# backplane-rev2.net
KiCad netlist of a schematic drawn in EAGLE
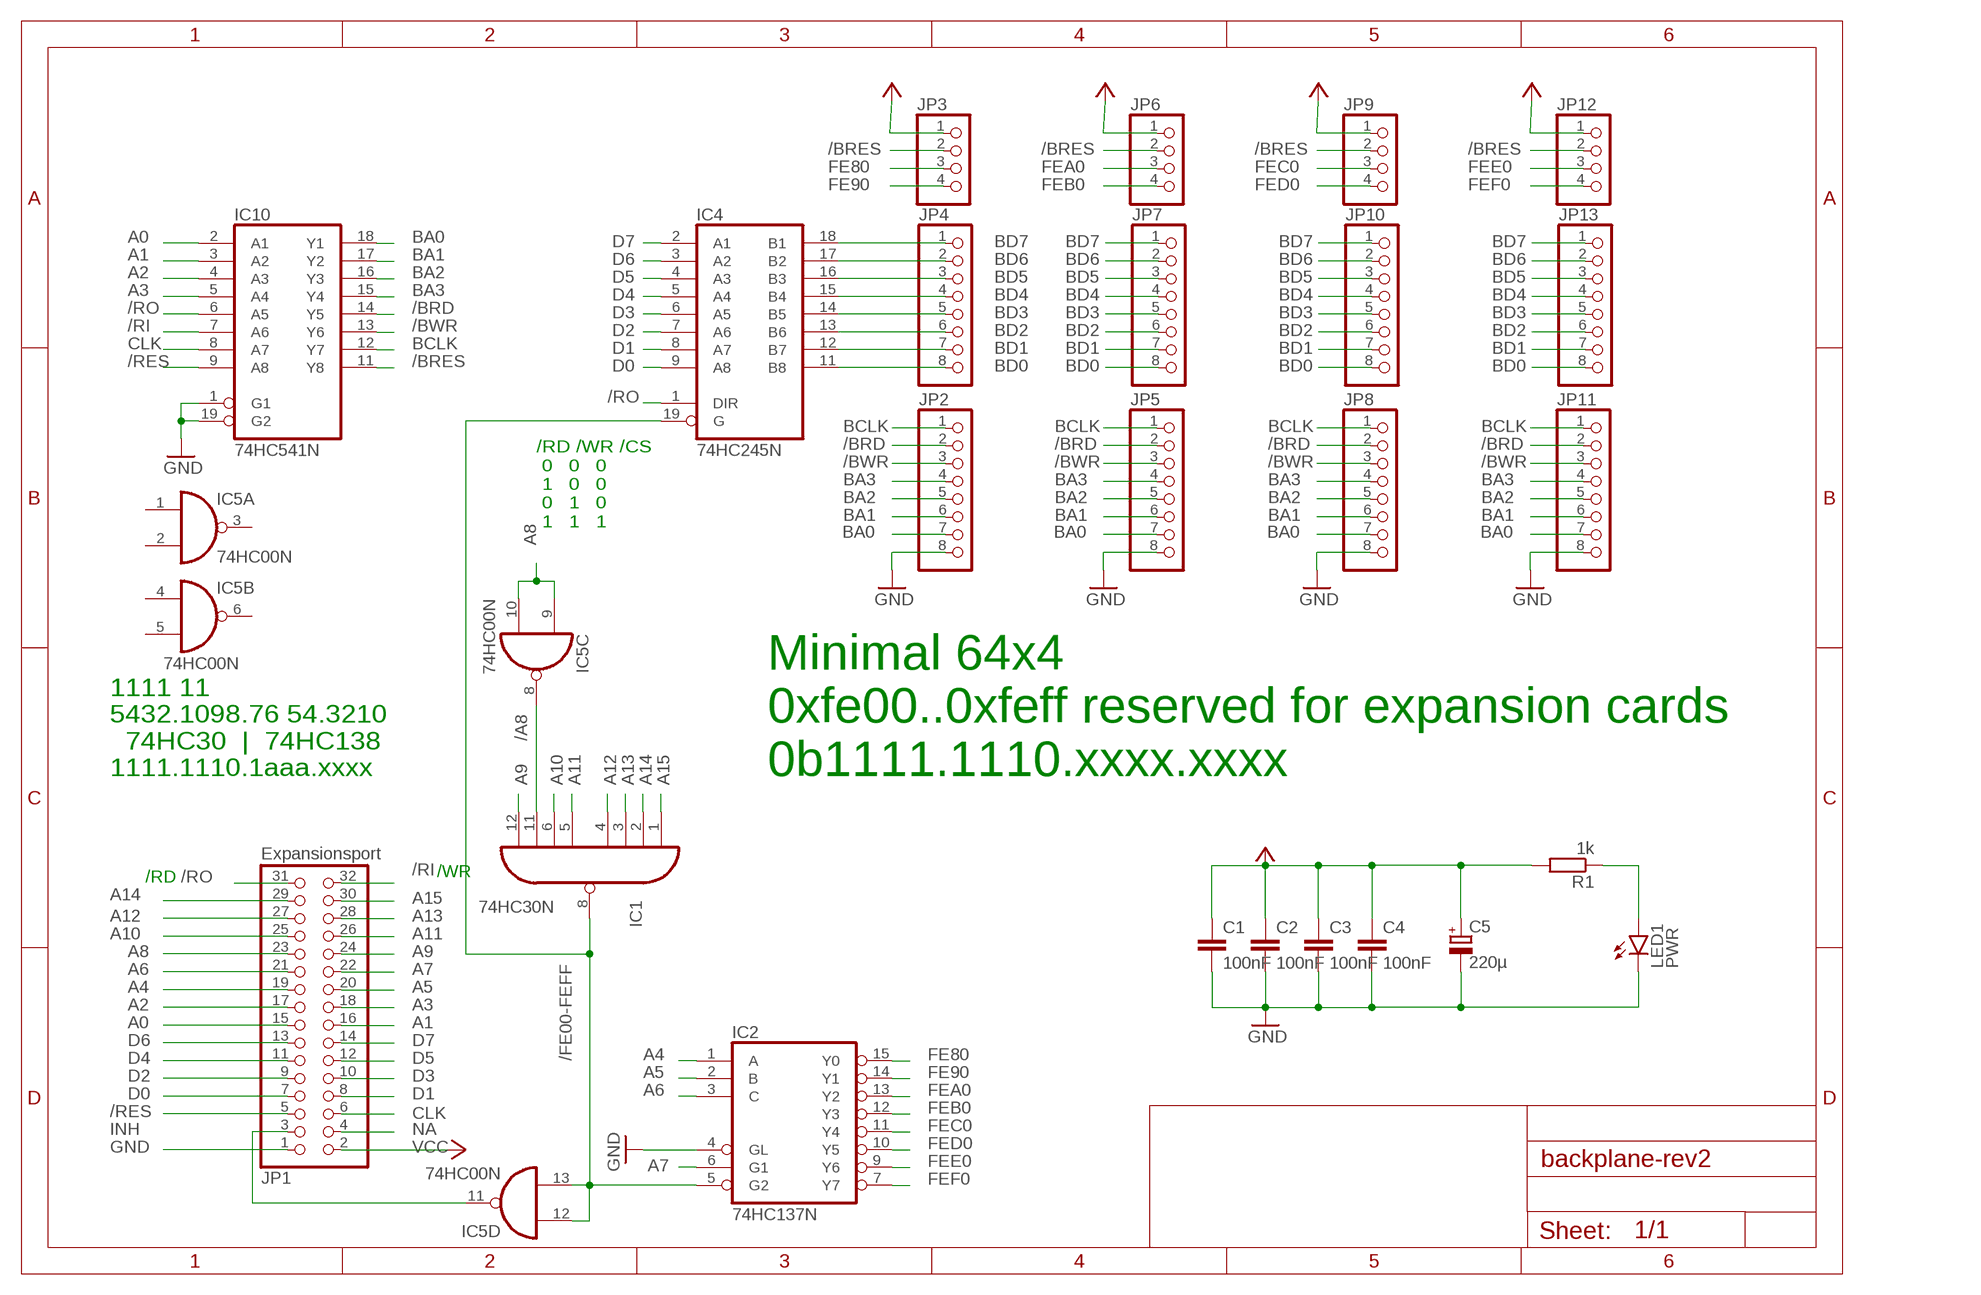
[diagram p0: schematic, sheet 1]

(export (version "E")
  (design (tool "Eeschema 10.0.6"))
  (components
    (comp (ref "C1")
      (value "100nF")
      (footprint "eagle-import:C050-025X075")
      (libsource (lib "eagle-import") (part "C-EU050-025X075"))
    )
    (comp (ref "C2")
      (value "100nF")
      (footprint "eagle-import:C050-025X075")
      (libsource (lib "eagle-import") (part "C-EU050-025X075"))
    )
    (comp (ref "C3")
      (value "100nF")
      (footprint "eagle-import:C050-025X075")
      (libsource (lib "eagle-import") (part "C-EU050-025X075"))
    )
    (comp (ref "C4")
      (value "100nF")
      (footprint "eagle-import:C050-025X075")
      (libsource (lib "eagle-import") (part "C-EU050-025X075"))
    )
    (comp (ref "C5")
      (value "220µ")
      (footprint "eagle-import:E3,5-8")
      (libsource (lib "eagle-import") (part "CPOL-EUE3.5-8"))
    )
    (comp (ref "IC1")
      (value "74HC30N")
      (footprint "eagle-import:DIL14")
      (libsource (lib "eagle-import") (part "7430NHC"))
    )
    (comp (ref "IC2")
      (value "74HC137N")
      (footprint "eagle-import:DIL16")
      (libsource (lib "eagle-import") (part "74137NHC"))
    )
    (comp (ref "IC4")
      (value "74HC245N")
      (footprint "eagle-import:DIL20")
      (libsource (lib "eagle-import") (part "74245NHC"))
    )
    (comp (ref "IC5")
      (value "74HC00N")
      (footprint "eagle-import:DIL14")
      (libsource (lib "eagle-import") (part "7400NHC"))
    )
    (comp (ref "IC10")
      (value "74HC541N")
      (footprint "eagle-import:DIL20")
      (libsource (lib "eagle-import") (part "74541NHC"))
    )
    (comp (ref "JP1")
      (value "Expansionsport")
      (footprint "eagle-import:2X16")
      (libsource (lib "eagle-import") (part "PINHD-2X16"))
    )
    (comp (ref "JP2")
      (value "PINHD-1X8")
      (footprint "eagle-import:1X08")
      (libsource (lib "eagle-import") (part "PINHD-1X8"))
    )
    (comp (ref "JP3")
      (value "PINHD-1X4")
      (footprint "eagle-import:1X04")
      (libsource (lib "eagle-import") (part "PINHD-1X4"))
    )
    (comp (ref "JP4")
      (value "PINHD-1X8")
      (footprint "eagle-import:1X08")
      (libsource (lib "eagle-import") (part "PINHD-1X8"))
    )
    (comp (ref "JP5")
      (value "PINHD-1X8")
      (footprint "eagle-import:1X08")
      (libsource (lib "eagle-import") (part "PINHD-1X8"))
    )
    (comp (ref "JP6")
      (value "PINHD-1X4")
      (footprint "eagle-import:1X04")
      (libsource (lib "eagle-import") (part "PINHD-1X4"))
    )
    (comp (ref "JP7")
      (value "PINHD-1X8")
      (footprint "eagle-import:1X08")
      (libsource (lib "eagle-import") (part "PINHD-1X8"))
    )
    (comp (ref "JP8")
      (value "PINHD-1X8")
      (footprint "eagle-import:1X08")
      (libsource (lib "eagle-import") (part "PINHD-1X8"))
    )
    (comp (ref "JP9")
      (value "PINHD-1X4")
      (footprint "eagle-import:1X04")
      (libsource (lib "eagle-import") (part "PINHD-1X4"))
    )
    (comp (ref "JP10")
      (value "PINHD-1X8")
      (footprint "eagle-import:1X08")
      (libsource (lib "eagle-import") (part "PINHD-1X8"))
    )
    (comp (ref "JP11")
      (value "PINHD-1X8")
      (footprint "eagle-import:1X08")
      (libsource (lib "eagle-import") (part "PINHD-1X8"))
    )
    (comp (ref "JP12")
      (value "PINHD-1X4")
      (footprint "eagle-import:1X04")
      (libsource (lib "eagle-import") (part "PINHD-1X4"))
    )
    (comp (ref "JP13")
      (value "PINHD-1X8")
      (footprint "eagle-import:1X08")
      (libsource (lib "eagle-import") (part "PINHD-1X8"))
    )
    (comp (ref "LED1")
      (value "PWR")
      (footprint "eagle-import:LED3MM")
      (libsource (lib "eagle-import") (part "LED3MM"))
    )
    (comp (ref "R1")
      (value "1k")
      (footprint "eagle-import:0207_10")
      (libsource (lib "eagle-import") (part "R-EU_0207/10"))
    )
  )
  (nets
    (net (code "1") (name "/A0") (class "Default")
      (node (ref "IC10") (pin "2") (pinfunction "A1_2") (pintype "input"))
      (node (ref "JP1") (pin "15") (pinfunction "15_15") (pintype "passive"))
    )
    (net (code "2") (name "/A1") (class "Default")
      (node (ref "IC10") (pin "3") (pinfunction "A2_3") (pintype "input"))
      (node (ref "JP1") (pin "16") (pinfunction "16_16") (pintype "passive"))
    )
    (net (code "3") (name "/A2") (class "Default")
      (node (ref "IC10") (pin "4") (pinfunction "A3_4") (pintype "input"))
      (node (ref "JP1") (pin "17") (pinfunction "17_17") (pintype "passive"))
    )
    (net (code "4") (name "/A3") (class "Default")
      (node (ref "IC10") (pin "5") (pinfunction "A4_5") (pintype "input"))
      (node (ref "JP1") (pin "18") (pinfunction "18_18") (pintype "passive"))
    )
    (net (code "5") (name "/A4") (class "Default")
      (node (ref "IC2") (pin "1") (pinfunction "A_1") (pintype "input"))
      (node (ref "JP1") (pin "19") (pinfunction "19_19") (pintype "passive"))
    )
    (net (code "6") (name "/A5") (class "Default")
      (node (ref "IC2") (pin "2") (pinfunction "B_2") (pintype "input"))
      (node (ref "JP1") (pin "20") (pinfunction "20_20") (pintype "passive"))
    )
    (net (code "7") (name "/A6") (class "Default")
      (node (ref "IC2") (pin "3") (pinfunction "C_3") (pintype "input"))
      (node (ref "JP1") (pin "21") (pinfunction "21_21") (pintype "passive"))
    )
    (net (code "8") (name "/A7") (class "Default")
      (node (ref "IC2") (pin "6") (pinfunction "G1_6") (pintype "input"))
      (node (ref "JP1") (pin "22") (pinfunction "22_22") (pintype "passive"))
    )
    (net (code "9") (name "/A8") (class "Default")
      (node (ref "IC5") (pin "10") (pinfunction "I1_10") (pintype "input"))
      (node (ref "IC5") (pin "9") (pinfunction "I0_9") (pintype "input"))
      (node (ref "JP1") (pin "23") (pinfunction "23_23") (pintype "passive"))
    )
    (net (code "10") (name "/A9") (class "Default")
      (node (ref "IC1") (pin "12") (pinfunction "I7_12") (pintype "input"))
      (node (ref "JP1") (pin "24") (pinfunction "24_24") (pintype "passive"))
    )
    (net (code "11") (name "/A10") (class "Default")
      (node (ref "IC1") (pin "6") (pinfunction "I5_6") (pintype "input"))
      (node (ref "JP1") (pin "25") (pinfunction "25_25") (pintype "passive"))
    )
    (net (code "12") (name "/A11") (class "Default")
      (node (ref "IC1") (pin "5") (pinfunction "I4_5") (pintype "input"))
      (node (ref "JP1") (pin "26") (pinfunction "26_26") (pintype "passive"))
    )
    (net (code "13") (name "/A12") (class "Default")
      (node (ref "IC1") (pin "4") (pinfunction "I3_4") (pintype "input"))
      (node (ref "JP1") (pin "27") (pinfunction "27_27") (pintype "passive"))
    )
    (net (code "14") (name "/A13") (class "Default")
      (node (ref "IC1") (pin "3") (pinfunction "I2_3") (pintype "input"))
      (node (ref "JP1") (pin "28") (pinfunction "28_28") (pintype "passive"))
    )
    (net (code "15") (name "/A14") (class "Default")
      (node (ref "IC1") (pin "2") (pinfunction "I1_2") (pintype "input"))
      (node (ref "JP1") (pin "29") (pinfunction "29_29") (pintype "passive"))
    )
    (net (code "16") (name "/A15") (class "Default")
      (node (ref "IC1") (pin "1") (pinfunction "I0_1") (pintype "input"))
      (node (ref "JP1") (pin "30") (pinfunction "30_30") (pintype "passive"))
    )
    (net (code "17") (name "/BA0") (class "Default")
      (node (ref "IC10") (pin "18") (pinfunction "Y1_18") (pintype "tri_state"))
      (node (ref "JP11") (pin "7") (pinfunction "7_7") (pintype "passive"))
      (node (ref "JP2") (pin "7") (pinfunction "7_7") (pintype "passive"))
      (node (ref "JP5") (pin "7") (pinfunction "7_7") (pintype "passive"))
      (node (ref "JP8") (pin "7") (pinfunction "7_7") (pintype "passive"))
    )
    (net (code "18") (name "/BA1") (class "Default")
      (node (ref "IC10") (pin "17") (pinfunction "Y2_17") (pintype "tri_state"))
      (node (ref "JP11") (pin "6") (pinfunction "6_6") (pintype "passive"))
      (node (ref "JP2") (pin "6") (pinfunction "6_6") (pintype "passive"))
      (node (ref "JP5") (pin "6") (pinfunction "6_6") (pintype "passive"))
      (node (ref "JP8") (pin "6") (pinfunction "6_6") (pintype "passive"))
    )
    (net (code "19") (name "/BA2") (class "Default")
      (node (ref "IC10") (pin "16") (pinfunction "Y3_16") (pintype "tri_state"))
      (node (ref "JP11") (pin "5") (pinfunction "5_5") (pintype "passive"))
      (node (ref "JP2") (pin "5") (pinfunction "5_5") (pintype "passive"))
      (node (ref "JP5") (pin "5") (pinfunction "5_5") (pintype "passive"))
      (node (ref "JP8") (pin "5") (pinfunction "5_5") (pintype "passive"))
    )
    (net (code "20") (name "/BA3") (class "Default")
      (node (ref "IC10") (pin "15") (pinfunction "Y4_15") (pintype "tri_state"))
      (node (ref "JP11") (pin "4") (pinfunction "4_4") (pintype "passive"))
      (node (ref "JP2") (pin "4") (pinfunction "4_4") (pintype "passive"))
      (node (ref "JP5") (pin "4") (pinfunction "4_4") (pintype "passive"))
      (node (ref "JP8") (pin "4") (pinfunction "4_4") (pintype "passive"))
    )
    (net (code "21") (name "/BCLK") (class "Default")
      (node (ref "IC10") (pin "12") (pinfunction "Y7_12") (pintype "tri_state"))
      (node (ref "JP11") (pin "1") (pinfunction "1_1") (pintype "passive"))
      (node (ref "JP2") (pin "1") (pinfunction "1_1") (pintype "passive"))
      (node (ref "JP5") (pin "1") (pinfunction "1_1") (pintype "passive"))
      (node (ref "JP8") (pin "1") (pinfunction "1_1") (pintype "passive"))
    )
    (net (code "22") (name "/BD0") (class "Default")
      (node (ref "IC4") (pin "11") (pinfunction "B8_11") (pintype "bidirectional"))
      (node (ref "JP10") (pin "8") (pinfunction "8_8") (pintype "passive"))
      (node (ref "JP13") (pin "8") (pinfunction "8_8") (pintype "passive"))
      (node (ref "JP4") (pin "8") (pinfunction "8_8") (pintype "passive"))
      (node (ref "JP7") (pin "8") (pinfunction "8_8") (pintype "passive"))
    )
    (net (code "23") (name "/BD1") (class "Default")
      (node (ref "IC4") (pin "12") (pinfunction "B7_12") (pintype "bidirectional"))
      (node (ref "JP10") (pin "7") (pinfunction "7_7") (pintype "passive"))
      (node (ref "JP13") (pin "7") (pinfunction "7_7") (pintype "passive"))
      (node (ref "JP4") (pin "7") (pinfunction "7_7") (pintype "passive"))
      (node (ref "JP7") (pin "7") (pinfunction "7_7") (pintype "passive"))
    )
    (net (code "24") (name "/BD2") (class "Default")
      (node (ref "IC4") (pin "13") (pinfunction "B6_13") (pintype "bidirectional"))
      (node (ref "JP10") (pin "6") (pinfunction "6_6") (pintype "passive"))
      (node (ref "JP13") (pin "6") (pinfunction "6_6") (pintype "passive"))
      (node (ref "JP4") (pin "6") (pinfunction "6_6") (pintype "passive"))
      (node (ref "JP7") (pin "6") (pinfunction "6_6") (pintype "passive"))
    )
    (net (code "25") (name "/BD3") (class "Default")
      (node (ref "IC4") (pin "14") (pinfunction "B5_14") (pintype "bidirectional"))
      (node (ref "JP10") (pin "5") (pinfunction "5_5") (pintype "passive"))
      (node (ref "JP13") (pin "5") (pinfunction "5_5") (pintype "passive"))
      (node (ref "JP4") (pin "5") (pinfunction "5_5") (pintype "passive"))
      (node (ref "JP7") (pin "5") (pinfunction "5_5") (pintype "passive"))
    )
    (net (code "26") (name "/BD4") (class "Default")
      (node (ref "IC4") (pin "15") (pinfunction "B4_15") (pintype "bidirectional"))
      (node (ref "JP10") (pin "4") (pinfunction "4_4") (pintype "passive"))
      (node (ref "JP13") (pin "4") (pinfunction "4_4") (pintype "passive"))
      (node (ref "JP4") (pin "4") (pinfunction "4_4") (pintype "passive"))
      (node (ref "JP7") (pin "4") (pinfunction "4_4") (pintype "passive"))
    )
    (net (code "27") (name "/BD5") (class "Default")
      (node (ref "IC4") (pin "16") (pinfunction "B3_16") (pintype "bidirectional"))
      (node (ref "JP10") (pin "3") (pinfunction "3_3") (pintype "passive"))
      (node (ref "JP13") (pin "3") (pinfunction "3_3") (pintype "passive"))
      (node (ref "JP4") (pin "3") (pinfunction "3_3") (pintype "passive"))
      (node (ref "JP7") (pin "3") (pinfunction "3_3") (pintype "passive"))
    )
    (net (code "28") (name "/BD6") (class "Default")
      (node (ref "IC4") (pin "17") (pinfunction "B2_17") (pintype "bidirectional"))
      (node (ref "JP10") (pin "2") (pinfunction "2_2") (pintype "passive"))
      (node (ref "JP13") (pin "2") (pinfunction "2_2") (pintype "passive"))
      (node (ref "JP4") (pin "2") (pinfunction "2_2") (pintype "passive"))
      (node (ref "JP7") (pin "2") (pinfunction "2_2") (pintype "passive"))
    )
    (net (code "29") (name "/BD7") (class "Default")
      (node (ref "IC4") (pin "18") (pinfunction "B1_18") (pintype "bidirectional"))
      (node (ref "JP10") (pin "1") (pinfunction "1_1") (pintype "passive"))
      (node (ref "JP13") (pin "1") (pinfunction "1_1") (pintype "passive"))
      (node (ref "JP4") (pin "1") (pinfunction "1_1") (pintype "passive"))
      (node (ref "JP7") (pin "1") (pinfunction "1_1") (pintype "passive"))
    )
    (net (code "30") (name "/CLK") (class "Default")
      (node (ref "IC10") (pin "8") (pinfunction "A7_8") (pintype "input"))
      (node (ref "JP1") (pin "6") (pinfunction "6_6") (pintype "passive"))
    )
    (net (code "31") (name "/D0") (class "Default")
      (node (ref "IC4") (pin "9") (pinfunction "A8_9") (pintype "bidirectional"))
      (node (ref "JP1") (pin "7") (pinfunction "7_7") (pintype "passive"))
    )
    (net (code "32") (name "/D1") (class "Default")
      (node (ref "IC4") (pin "8") (pinfunction "A7_8") (pintype "bidirectional"))
      (node (ref "JP1") (pin "8") (pinfunction "8_8") (pintype "passive"))
    )
    (net (code "33") (name "/D2") (class "Default")
      (node (ref "IC4") (pin "7") (pinfunction "A6_7") (pintype "bidirectional"))
      (node (ref "JP1") (pin "9") (pinfunction "9_9") (pintype "passive"))
    )
    (net (code "34") (name "/D3") (class "Default")
      (node (ref "IC4") (pin "6") (pinfunction "A5_6") (pintype "bidirectional"))
      (node (ref "JP1") (pin "10") (pinfunction "10_10") (pintype "passive"))
    )
    (net (code "35") (name "/D4") (class "Default")
      (node (ref "IC4") (pin "5") (pinfunction "A4_5") (pintype "bidirectional"))
      (node (ref "JP1") (pin "11") (pinfunction "11_11") (pintype "passive"))
    )
    (net (code "36") (name "/D5") (class "Default")
      (node (ref "IC4") (pin "4") (pinfunction "A3_4") (pintype "bidirectional"))
      (node (ref "JP1") (pin "12") (pinfunction "12_12") (pintype "passive"))
    )
    (net (code "37") (name "/D6") (class "Default")
      (node (ref "IC4") (pin "3") (pinfunction "A2_3") (pintype "bidirectional"))
      (node (ref "JP1") (pin "13") (pinfunction "13_13") (pintype "passive"))
    )
    (net (code "38") (name "/D7") (class "Default")
      (node (ref "IC4") (pin "2") (pinfunction "A1_2") (pintype "bidirectional"))
      (node (ref "JP1") (pin "14") (pinfunction "14_14") (pintype "passive"))
    )
    (net (code "39") (name "/FE80") (class "Default")
      (node (ref "IC2") (pin "15") (pinfunction "Y0_15") (pintype "output"))
      (node (ref "JP3") (pin "3") (pinfunction "3_3") (pintype "passive"))
    )
    (net (code "40") (name "/FE90") (class "Default")
      (node (ref "IC2") (pin "14") (pinfunction "Y1_14") (pintype "output"))
      (node (ref "JP3") (pin "4") (pinfunction "4_4") (pintype "passive"))
    )
    (net (code "41") (name "/FEA0") (class "Default")
      (node (ref "IC2") (pin "13") (pinfunction "Y2_13") (pintype "output"))
      (node (ref "JP6") (pin "3") (pinfunction "3_3") (pintype "passive"))
    )
    (net (code "42") (name "/FEB0") (class "Default")
      (node (ref "IC2") (pin "12") (pinfunction "Y3_12") (pintype "output"))
      (node (ref "JP6") (pin "4") (pinfunction "4_4") (pintype "passive"))
    )
    (net (code "43") (name "/FEC0") (class "Default")
      (node (ref "IC2") (pin "11") (pinfunction "Y4_11") (pintype "output"))
      (node (ref "JP9") (pin "3") (pinfunction "3_3") (pintype "passive"))
    )
    (net (code "44") (name "/FED0") (class "Default")
      (node (ref "IC2") (pin "10") (pinfunction "Y5_10") (pintype "output"))
      (node (ref "JP9") (pin "4") (pinfunction "4_4") (pintype "passive"))
    )
    (net (code "45") (name "/FEE0") (class "Default")
      (node (ref "IC2") (pin "9") (pinfunction "Y6_9") (pintype "output"))
      (node (ref "JP12") (pin "3") (pinfunction "3_3") (pintype "passive"))
    )
    (net (code "46") (name "/FEF0") (class "Default")
      (node (ref "IC2") (pin "7") (pinfunction "Y7_7") (pintype "output"))
      (node (ref "JP12") (pin "4") (pinfunction "4_4") (pintype "passive"))
    )
    (net (code "47") (name "/INH") (class "Default")
      (node (ref "IC5") (pin "11") (pinfunction "O_11") (pintype "output"))
      (node (ref "JP1") (pin "3") (pinfunction "3_3") (pintype "passive"))
    )
    (net (code "48") (name "/NA") (class "Default")
      (node (ref "JP1") (pin "4") (pinfunction "4_4") (pintype "passive"))
    )
    (net (code "49") (name "/{slash}A8") (class "Default")
      (node (ref "IC1") (pin "11") (pinfunction "I6_11") (pintype "input"))
      (node (ref "IC5") (pin "8") (pinfunction "O_8") (pintype "output"))
    )
    (net (code "50") (name "/{slash}BRD") (class "Default")
      (node (ref "IC10") (pin "14") (pinfunction "Y5_14") (pintype "tri_state"))
      (node (ref "JP11") (pin "2") (pinfunction "2_2") (pintype "passive"))
      (node (ref "JP2") (pin "2") (pinfunction "2_2") (pintype "passive"))
      (node (ref "JP5") (pin "2") (pinfunction "2_2") (pintype "passive"))
      (node (ref "JP8") (pin "2") (pinfunction "2_2") (pintype "passive"))
    )
    (net (code "51") (name "/{slash}BRES") (class "Default")
      (node (ref "IC10") (pin "11") (pinfunction "Y8_11") (pintype "tri_state"))
      (node (ref "JP12") (pin "2") (pinfunction "2_2") (pintype "passive"))
      (node (ref "JP3") (pin "2") (pinfunction "2_2") (pintype "passive"))
      (node (ref "JP6") (pin "2") (pinfunction "2_2") (pintype "passive"))
      (node (ref "JP9") (pin "2") (pinfunction "2_2") (pintype "passive"))
    )
    (net (code "52") (name "/{slash}BWR") (class "Default")
      (node (ref "IC10") (pin "13") (pinfunction "Y6_13") (pintype "tri_state"))
      (node (ref "JP11") (pin "3") (pinfunction "3_3") (pintype "passive"))
      (node (ref "JP2") (pin "3") (pinfunction "3_3") (pintype "passive"))
      (node (ref "JP5") (pin "3") (pinfunction "3_3") (pintype "passive"))
      (node (ref "JP8") (pin "3") (pinfunction "3_3") (pintype "passive"))
    )
    (net (code "53") (name "/{slash}FE00-FEFF") (class "Default")
      (node (ref "IC1") (pin "8") (pinfunction "O_8") (pintype "output"))
      (node (ref "IC2") (pin "5") (pinfunction "G2_5") (pintype "input"))
      (node (ref "IC4") (pin "19") (pinfunction "G_19") (pintype "input"))
      (node (ref "IC5") (pin "12") (pinfunction "I0_12") (pintype "input"))
      (node (ref "IC5") (pin "13") (pinfunction "I1_13") (pintype "input"))
    )
    (net (code "54") (name "/{slash}RES") (class "Default")
      (node (ref "IC10") (pin "9") (pinfunction "A8_9") (pintype "input"))
      (node (ref "JP1") (pin "5") (pinfunction "5_5") (pintype "passive"))
    )
    (net (code "55") (name "/{slash}RI") (class "Default")
      (node (ref "IC10") (pin "7") (pinfunction "A6_7") (pintype "input"))
      (node (ref "JP1") (pin "32") (pinfunction "32_32") (pintype "passive"))
    )
    (net (code "56") (name "/{slash}RO") (class "Default")
      (node (ref "IC10") (pin "6") (pinfunction "A5_6") (pintype "input"))
      (node (ref "IC4") (pin "1") (pinfunction "DIR_1") (pintype "input"))
      (node (ref "JP1") (pin "31") (pinfunction "31_31") (pintype "passive"))
    )
    (net (code "57") (name "GND") (class "Default")
      (node (ref "C1") (pin "2") (pinfunction "2_2") (pintype "passive"))
      (node (ref "C2") (pin "2") (pinfunction "2_2") (pintype "passive"))
      (node (ref "C3") (pin "2") (pinfunction "2_2") (pintype "passive"))
      (node (ref "C4") (pin "2") (pinfunction "2_2") (pintype "passive"))
      (node (ref "C5") (pin "-") (pinfunction "-_-") (pintype "passive"))
      (node (ref "IC10") (pin "1") (pinfunction "G1_1") (pintype "input"))
      (node (ref "IC10") (pin "19") (pinfunction "G2_19") (pintype "input"))
      (node (ref "IC2") (pin "4") (pinfunction "GL_4") (pintype "input"))
      (node (ref "JP1") (pin "1") (pinfunction "1_1") (pintype "passive"))
      (node (ref "JP11") (pin "8") (pinfunction "8_8") (pintype "passive"))
      (node (ref "JP2") (pin "8") (pinfunction "8_8") (pintype "passive"))
      (node (ref "JP5") (pin "8") (pinfunction "8_8") (pintype "passive"))
      (node (ref "JP8") (pin "8") (pinfunction "8_8") (pintype "passive"))
      (node (ref "LED1") (pin "K") (pinfunction "C_K") (pintype "passive"))
    )
    (net (code "58") (name "Net-(LED1-PadA)") (class "Default")
      (node (ref "LED1") (pin "A") (pinfunction "A_A") (pintype "passive"))
      (node (ref "R1") (pin "1") (pinfunction "1_1") (pintype "passive"))
    )
    (net (code "59") (name "VCC") (class "Default")
      (node (ref "C1") (pin "1") (pinfunction "1_1") (pintype "passive"))
      (node (ref "C2") (pin "1") (pinfunction "1_1") (pintype "passive"))
      (node (ref "C3") (pin "1") (pinfunction "1_1") (pintype "passive"))
      (node (ref "C4") (pin "1") (pinfunction "1_1") (pintype "passive"))
      (node (ref "C5") (pin "+") (pinfunction "+_+") (pintype "passive"))
      (node (ref "JP1") (pin "2") (pinfunction "2_2") (pintype "passive"))
      (node (ref "JP12") (pin "1") (pinfunction "1_1") (pintype "passive"))
      (node (ref "JP3") (pin "1") (pinfunction "1_1") (pintype "passive"))
      (node (ref "JP6") (pin "1") (pinfunction "1_1") (pintype "passive"))
      (node (ref "JP9") (pin "1") (pinfunction "1_1") (pintype "passive"))
      (node (ref "R1") (pin "2") (pinfunction "2_2") (pintype "passive"))
    )
    (net (code "60") (name "unconnected-(IC5A-I0-Pad1)") (class "Default")
      (node (ref "IC5") (pin "1") (pinfunction "I0_1") (pintype "input"))
    )
    (net (code "61") (name "unconnected-(IC5A-I1-Pad2)") (class "Default")
      (node (ref "IC5") (pin "2") (pinfunction "I1_2") (pintype "input"))
    )
    (net (code "62") (name "unconnected-(IC5A-O-Pad3)") (class "Default")
      (node (ref "IC5") (pin "3") (pinfunction "O_3") (pintype "output"))
    )
    (net (code "63") (name "unconnected-(IC5B-I0-Pad4)") (class "Default")
      (node (ref "IC5") (pin "4") (pinfunction "I0_4") (pintype "input"))
    )
    (net (code "64") (name "unconnected-(IC5B-I1-Pad5)") (class "Default")
      (node (ref "IC5") (pin "5") (pinfunction "I1_5") (pintype "input"))
    )
    (net (code "65") (name "unconnected-(IC5B-O-Pad6)") (class "Default")
      (node (ref "IC5") (pin "6") (pinfunction "O_6") (pintype "output"))
    )
  )
)
